# PIC.net
KiCad netlist of a schematic drawn in Altium Designer
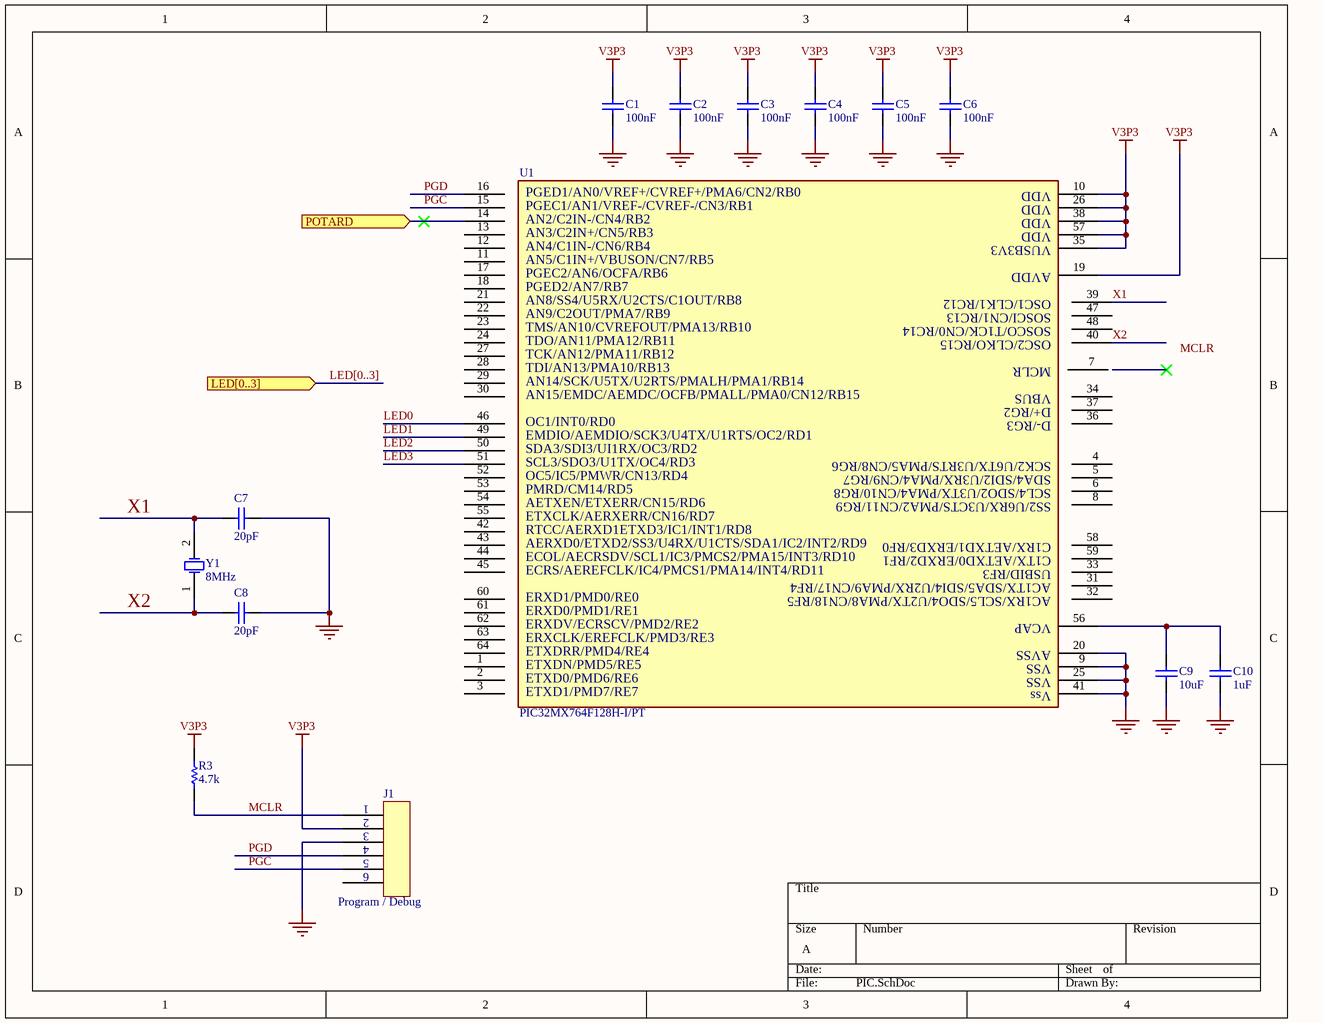
[diagram p0: PIC.SchDoc]

(export (version "E")
  (design (tool "Eeschema 10.0.6"))
  (components
    (comp (ref "C1")
      (value "100nF")
      (footprint "PcbLib_2:CAPC1608N")
      (description "Capacitor")
      (fields (field (name "PUBLISHER") "Altium Limited"))
      (libsource (lib "Miscellaneous Devices") (part "Cap"))
    )
    (comp (ref "C2")
      (value "100nF")
      (footprint "PcbLib_2:CAPC1608N")
      (description "Capacitor")
      (fields (field (name "PUBLISHER") "Altium Limited"))
      (libsource (lib "Miscellaneous Devices") (part "Cap"))
    )
    (comp (ref "C3")
      (value "100nF")
      (footprint "PcbLib_2:CAPC1608N")
      (description "Capacitor")
      (fields (field (name "PUBLISHER") "Altium Limited"))
      (libsource (lib "Miscellaneous Devices") (part "Cap"))
    )
    (comp (ref "C4")
      (value "100nF")
      (footprint "PcbLib_2:CAPC1608N")
      (description "Capacitor")
      (fields (field (name "PUBLISHER") "Altium Limited"))
      (libsource (lib "Miscellaneous Devices") (part "Cap"))
    )
    (comp (ref "C5")
      (value "100nF")
      (footprint "PcbLib_2:CAPC1608N")
      (description "Capacitor")
      (fields (field (name "PUBLISHER") "Altium Limited"))
      (libsource (lib "Miscellaneous Devices") (part "Cap"))
    )
    (comp (ref "C6")
      (value "100nF")
      (footprint "PcbLib_2:CAPC1608N")
      (description "Capacitor")
      (fields (field (name "PUBLISHER") "Altium Limited"))
      (libsource (lib "Miscellaneous Devices") (part "Cap"))
    )
    (comp (ref "C7")
      (value "20pF")
      (footprint "PcbLib_2:CAPC1608N")
      (description "Capacitor")
      (fields (field (name "PUBLISHER") "Altium Limited"))
      (libsource (lib "Miscellaneous Devices") (part "Cap"))
    )
    (comp (ref "C8")
      (value "20pF")
      (footprint "PcbLib_2:CAPC1608N")
      (description "Capacitor")
      (fields (field (name "PUBLISHER") "Altium Limited"))
      (libsource (lib "Miscellaneous Devices") (part "Cap"))
    )
    (comp (ref "C9")
      (value "10uF")
      (footprint "PcbLib_2:CAPC2012N")
      (description "Capacitor")
      (fields (field (name "PUBLISHER") "Altium Limited"))
      (libsource (lib "Miscellaneous Devices") (part "Cap"))
    )
    (comp (ref "C10")
      (value "1uF")
      (footprint "PcbLib_2:CAPC1608N")
      (description "Capacitor")
      (fields (field (name "PUBLISHER") "Altium Limited"))
      (libsource (lib "Miscellaneous Devices") (part "Cap"))
    )
    (comp (ref "J1")
      (value "Program / Debug")
      (footprint "PcbLib_2:RJ12_90")
      (libsource (lib "LibSch") (part "Program / Debug"))
    )
    (comp (ref "R3")
      (value "4.7k")
      (footprint "PcbLib_2:RESC1608N")
      (description "Resistor")
      (fields (field (name "PUBLISHER") "Altium Limited"))
      (libsource (lib "Miscellaneous Devices") (part "Res1"))
    )
    (comp (ref "U1")
      (value "PIC32MX764F128H-I/PT")
      (footprint "PcbLib_1:PIC")
      (libsource (lib "Schlib1") (part "Pic - 32MX"))
    )
    (comp (ref "Y1")
      (value "8MHz")
      (footprint "PcbLib_1:HC49/4H SMX CRYSTAL")
      (description "Crystal Oscillator")
      (fields (field (name "PUBLISHER") "Altium Limited"))
      (libsource (lib "Miscellaneous Devices") (part "XTAL"))
    )
  )
  (nets
    (net (code "6") (name "/MCLR") (class "Default")
      (node (ref "R3") (pin "1") (pinfunction "1_1") (pintype "passive"))
    )
    (net (code "10") (name "/X1") (class "Default")
      (node (ref "C7") (pin "1") (pinfunction "1_1") (pintype "passive"))
      (node (ref "Y1") (pin "2") (pinfunction "OSC2_2") (pintype "passive"))
    )
    (net (code "11") (name "/X2") (class "Default")
      (node (ref "C8") (pin "1") (pinfunction "1_1") (pintype "passive"))
      (node (ref "Y1") (pin "1") (pinfunction "OSC1_1") (pintype "passive"))
    )
    (net (code "12") (name "<NO NET>") (class "Default")
      (node (ref "C1") (pin "1") (pinfunction "1_1") (pintype "passive"))
      (node (ref "C10") (pin "1") (pinfunction "1_1") (pintype "passive"))
      (node (ref "C2") (pin "1") (pinfunction "1_1") (pintype "passive"))
      (node (ref "C3") (pin "1") (pinfunction "1_1") (pintype "passive"))
      (node (ref "C4") (pin "1") (pinfunction "1_1") (pintype "passive"))
      (node (ref "C5") (pin "1") (pinfunction "1_1") (pintype "passive"))
      (node (ref "C6") (pin "1") (pinfunction "1_1") (pintype "passive"))
      (node (ref "C9") (pin "1") (pinfunction "1_1") (pintype "passive"))
    )
    (net (code "13") (name "GND") (class "Default")
      (node (ref "C7") (pin "2") (pinfunction "2_2") (pintype "passive"))
      (node (ref "C8") (pin "2") (pinfunction "2_2") (pintype "passive"))
    )
    (net (code "14") (name "Net-(C10-Pad2)") (class "Default")
      (node (ref "C10") (pin "2") (pinfunction "2_2") (pintype "passive"))
      (node (ref "C9") (pin "2") (pinfunction "2_2") (pintype "passive"))
    )
    (net (code "15") (name "V3P3") (class "Default")
      (node (ref "C1") (pin "2") (pinfunction "2_2") (pintype "passive"))
      (node (ref "C2") (pin "2") (pinfunction "2_2") (pintype "passive"))
      (node (ref "C3") (pin "2") (pinfunction "2_2") (pintype "passive"))
      (node (ref "C4") (pin "2") (pinfunction "2_2") (pintype "passive"))
      (node (ref "C5") (pin "2") (pinfunction "2_2") (pintype "passive"))
      (node (ref "C6") (pin "2") (pinfunction "2_2") (pintype "passive"))
      (node (ref "R3") (pin "2") (pinfunction "2_2") (pintype "passive"))
    )
    (net (code "16") (name "unconnected-(U1-Pad1)") (class "Default")
      (node (ref "U1") (pin "1") (pinfunction "1_1") (pintype "passive"))
    )
    (net (code "17") (name "unconnected-(U1-Pad2)") (class "Default")
      (node (ref "U1") (pin "2") (pinfunction "2_2") (pintype "passive"))
    )
    (net (code "18") (name "unconnected-(U1-Pad3)") (class "Default")
      (node (ref "U1") (pin "3") (pinfunction "3_3") (pintype "passive"))
    )
    (net (code "19") (name "unconnected-(U1-Pad4)") (class "Default")
      (node (ref "U1") (pin "4") (pinfunction "4_4") (pintype "passive"))
    )
    (net (code "20") (name "unconnected-(U1-Pad5)") (class "Default")
      (node (ref "U1") (pin "5") (pinfunction "5_5") (pintype "passive"))
    )
    (net (code "21") (name "unconnected-(U1-Pad6)") (class "Default")
      (node (ref "U1") (pin "6") (pinfunction "6_6") (pintype "passive"))
    )
    (net (code "22") (name "unconnected-(U1-Pad7)") (class "Default")
      (node (ref "U1") (pin "7") (pinfunction "7_7") (pintype "passive"))
    )
    (net (code "23") (name "unconnected-(U1-Pad8)") (class "Default")
      (node (ref "U1") (pin "8") (pinfunction "8_8") (pintype "passive"))
    )
    (net (code "24") (name "unconnected-(U1-Pad9)") (class "Default")
      (node (ref "U1") (pin "9") (pinfunction "9_9") (pintype "passive"))
    )
    (net (code "25") (name "unconnected-(U1-Pad10)") (class "Default")
      (node (ref "U1") (pin "10") (pinfunction "10_10") (pintype "passive"))
    )
    (net (code "26") (name "unconnected-(U1-Pad11)") (class "Default")
      (node (ref "U1") (pin "11") (pinfunction "11_11") (pintype "passive"))
    )
    (net (code "27") (name "unconnected-(U1-Pad12)") (class "Default")
      (node (ref "U1") (pin "12") (pinfunction "12_12") (pintype "passive"))
    )
    (net (code "28") (name "unconnected-(U1-Pad13)") (class "Default")
      (node (ref "U1") (pin "13") (pinfunction "13_13") (pintype "passive"))
    )
    (net (code "29") (name "unconnected-(U1-Pad14)") (class "Default")
      (node (ref "U1") (pin "14") (pinfunction "14_14") (pintype "passive"))
    )
    (net (code "30") (name "unconnected-(U1-Pad15)") (class "Default")
      (node (ref "U1") (pin "15") (pinfunction "15_15") (pintype "passive"))
    )
    (net (code "31") (name "unconnected-(U1-Pad16)") (class "Default")
      (node (ref "U1") (pin "16") (pinfunction "16_16") (pintype "passive"))
    )
    (net (code "32") (name "unconnected-(U1-Pad17)") (class "Default")
      (node (ref "U1") (pin "17") (pinfunction "17_17") (pintype "passive"))
    )
    (net (code "33") (name "unconnected-(U1-Pad18)") (class "Default")
      (node (ref "U1") (pin "18") (pinfunction "18_18") (pintype "passive"))
    )
    (net (code "34") (name "unconnected-(U1-Pad19)") (class "Default")
      (node (ref "U1") (pin "19") (pinfunction "19_19") (pintype "passive"))
    )
    (net (code "35") (name "unconnected-(U1-Pad20)") (class "Default")
      (node (ref "U1") (pin "20") (pinfunction "20_20") (pintype "passive"))
    )
    (net (code "36") (name "unconnected-(U1-Pad21)") (class "Default")
      (node (ref "U1") (pin "21") (pinfunction "21_21") (pintype "passive"))
    )
    (net (code "37") (name "unconnected-(U1-Pad22)") (class "Default")
      (node (ref "U1") (pin "22") (pinfunction "22_22") (pintype "passive"))
    )
    (net (code "38") (name "unconnected-(U1-Pad23)") (class "Default")
      (node (ref "U1") (pin "23") (pinfunction "23_23") (pintype "passive"))
    )
    (net (code "39") (name "unconnected-(U1-Pad24)") (class "Default")
      (node (ref "U1") (pin "24") (pinfunction "24_24") (pintype "passive"))
    )
    (net (code "40") (name "unconnected-(U1-Pad25)") (class "Default")
      (node (ref "U1") (pin "25") (pinfunction "25_25") (pintype "passive"))
    )
    (net (code "41") (name "unconnected-(U1-Pad26)") (class "Default")
      (node (ref "U1") (pin "26") (pinfunction "26_26") (pintype "passive"))
    )
    (net (code "42") (name "unconnected-(U1-Pad27)") (class "Default")
      (node (ref "U1") (pin "27") (pinfunction "27_27") (pintype "passive"))
    )
    (net (code "43") (name "unconnected-(U1-Pad28)") (class "Default")
      (node (ref "U1") (pin "28") (pinfunction "28_28") (pintype "passive"))
    )
    (net (code "44") (name "unconnected-(U1-Pad29)") (class "Default")
      (node (ref "U1") (pin "29") (pinfunction "29_29") (pintype "passive"))
    )
    (net (code "45") (name "unconnected-(U1-Pad30)") (class "Default")
      (node (ref "U1") (pin "30") (pinfunction "30_30") (pintype "passive"))
    )
    (net (code "46") (name "unconnected-(U1-Pad31)") (class "Default")
      (node (ref "U1") (pin "31") (pinfunction "31_31") (pintype "passive"))
    )
    (net (code "47") (name "unconnected-(U1-Pad32)") (class "Default")
      (node (ref "U1") (pin "32") (pinfunction "32_32") (pintype "passive"))
    )
    (net (code "48") (name "unconnected-(U1-Pad33)") (class "Default")
      (node (ref "U1") (pin "33") (pinfunction "33_33") (pintype "passive"))
    )
    (net (code "49") (name "unconnected-(U1-Pad34)") (class "Default")
      (node (ref "U1") (pin "34") (pinfunction "34_34") (pintype "passive"))
    )
    (net (code "50") (name "unconnected-(U1-Pad35)") (class "Default")
      (node (ref "U1") (pin "35") (pinfunction "35_35") (pintype "passive"))
    )
    (net (code "51") (name "unconnected-(U1-Pad36)") (class "Default")
      (node (ref "U1") (pin "36") (pinfunction "36_36") (pintype "passive"))
    )
    (net (code "52") (name "unconnected-(U1-Pad37)") (class "Default")
      (node (ref "U1") (pin "37") (pinfunction "37_37") (pintype "passive"))
    )
    (net (code "53") (name "unconnected-(U1-Pad38)") (class "Default")
      (node (ref "U1") (pin "38") (pinfunction "38_38") (pintype "passive"))
    )
    (net (code "54") (name "unconnected-(U1-Pad39)") (class "Default")
      (node (ref "U1") (pin "39") (pinfunction "39_39") (pintype "passive"))
    )
    (net (code "55") (name "unconnected-(U1-Pad40)") (class "Default")
      (node (ref "U1") (pin "40") (pinfunction "40_40") (pintype "passive"))
    )
    (net (code "56") (name "unconnected-(U1-Pad41)") (class "Default")
      (node (ref "U1") (pin "41") (pinfunction "41_41") (pintype "passive"))
    )
    (net (code "57") (name "unconnected-(U1-Pad42)") (class "Default")
      (node (ref "U1") (pin "42") (pinfunction "42_42") (pintype "passive"))
    )
    (net (code "58") (name "unconnected-(U1-Pad43)") (class "Default")
      (node (ref "U1") (pin "43") (pinfunction "43_43") (pintype "passive"))
    )
    (net (code "59") (name "unconnected-(U1-Pad44)") (class "Default")
      (node (ref "U1") (pin "44") (pinfunction "44_44") (pintype "passive"))
    )
    (net (code "60") (name "unconnected-(U1-Pad45)") (class "Default")
      (node (ref "U1") (pin "45") (pinfunction "45_45") (pintype "passive"))
    )
    (net (code "61") (name "unconnected-(U1-Pad46)") (class "Default")
      (node (ref "U1") (pin "46") (pinfunction "46_46") (pintype "passive"))
    )
    (net (code "62") (name "unconnected-(U1-Pad47)") (class "Default")
      (node (ref "U1") (pin "47") (pinfunction "47_47") (pintype "passive"))
    )
    (net (code "63") (name "unconnected-(U1-Pad48)") (class "Default")
      (node (ref "U1") (pin "48") (pinfunction "48_48") (pintype "passive"))
    )
    (net (code "64") (name "unconnected-(U1-Pad49)") (class "Default")
      (node (ref "U1") (pin "49") (pinfunction "49_49") (pintype "passive"))
    )
    (net (code "65") (name "unconnected-(U1-Pad50)") (class "Default")
      (node (ref "U1") (pin "50") (pinfunction "50_50") (pintype "passive"))
    )
    (net (code "66") (name "unconnected-(U1-Pad51)") (class "Default")
      (node (ref "U1") (pin "51") (pinfunction "51_51") (pintype "passive"))
    )
    (net (code "67") (name "unconnected-(U1-Pad52)") (class "Default")
      (node (ref "U1") (pin "52") (pinfunction "52_52") (pintype "passive"))
    )
    (net (code "68") (name "unconnected-(U1-Pad53)") (class "Default")
      (node (ref "U1") (pin "53") (pinfunction "53_53") (pintype "passive"))
    )
    (net (code "69") (name "unconnected-(U1-Pad54)") (class "Default")
      (node (ref "U1") (pin "54") (pinfunction "54_54") (pintype "passive"))
    )
    (net (code "70") (name "unconnected-(U1-Pad55)") (class "Default")
      (node (ref "U1") (pin "55") (pinfunction "55_55") (pintype "passive"))
    )
    (net (code "71") (name "unconnected-(U1-Pad56)") (class "Default")
      (node (ref "U1") (pin "56") (pinfunction "56_56") (pintype "passive"))
    )
    (net (code "72") (name "unconnected-(U1-Pad57)") (class "Default")
      (node (ref "U1") (pin "57") (pinfunction "57_57") (pintype "passive"))
    )
    (net (code "73") (name "unconnected-(U1-Pad58)") (class "Default")
      (node (ref "U1") (pin "58") (pinfunction "58_58") (pintype "passive"))
    )
    (net (code "74") (name "unconnected-(U1-Pad59)") (class "Default")
      (node (ref "U1") (pin "59") (pinfunction "59_59") (pintype "passive"))
    )
    (net (code "75") (name "unconnected-(U1-Pad60)") (class "Default")
      (node (ref "U1") (pin "60") (pinfunction "60_60") (pintype "passive"))
    )
    (net (code "76") (name "unconnected-(U1-Pad61)") (class "Default")
      (node (ref "U1") (pin "61") (pinfunction "61_61") (pintype "passive"))
    )
    (net (code "77") (name "unconnected-(U1-Pad62)") (class "Default")
      (node (ref "U1") (pin "62") (pinfunction "62_62") (pintype "passive"))
    )
    (net (code "78") (name "unconnected-(U1-Pad63)") (class "Default")
      (node (ref "U1") (pin "63") (pinfunction "63_63") (pintype "passive"))
    )
    (net (code "79") (name "unconnected-(U1-Pad64)") (class "Default")
      (node (ref "U1") (pin "64") (pinfunction "64_64") (pintype "passive"))
    )
  )
)
